# RF.net
KiCad netlist of a schematic drawn in Altium Designer
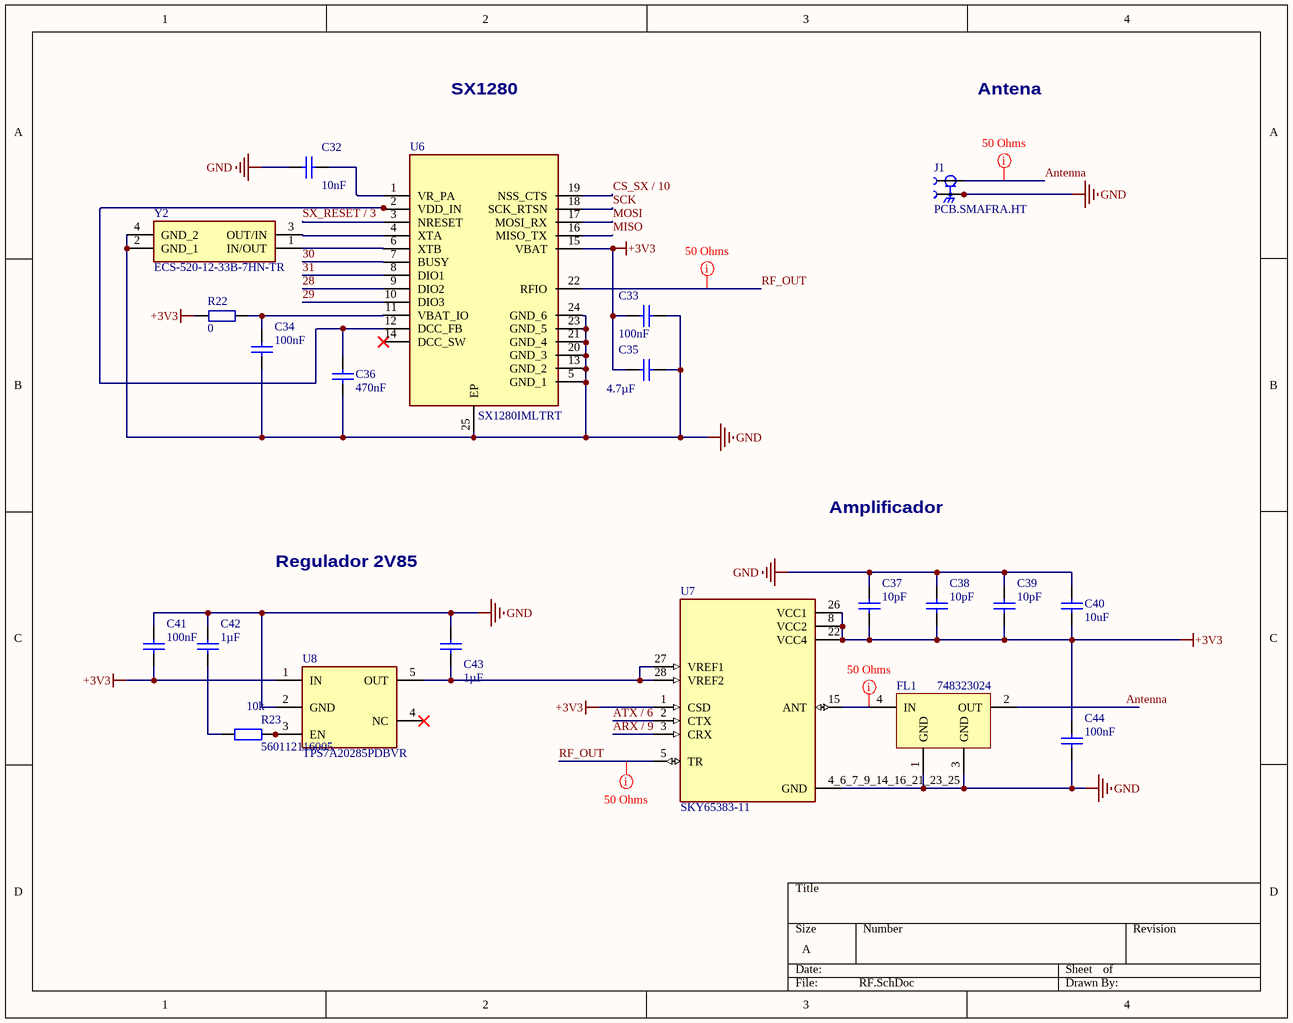
[diagram p0:  RF.SchDoc]

(export (version "E")
  (design (tool "Eeschema 10.0.6"))
  (components
    (comp (ref "C32")
      (value "10nF")
      (footprint "WCAP-CSGP_0603_L1.6W0.8H0.8_Reflow")
      (description "WCAP-CSGP Multilayer Ceramic Chip Capacitor, General Purpose, size 0603, X7R, 10nF, 25VDC")
      (fields
        (field (name "MANUFACTURER") "Wurth Elektronik")
        (field (name "MANUFACTURER PART NUMBER") "885012206065")
      )
      (libsource (lib "LEEM UPM") (part "885012209047R"))
    )
    (comp (ref "C33")
      (value "100nF")
      (footprint "WCAP-CSGP_0603_L1.6W0.8H0.8_Reflow")
      (description "WCAP-CSGP Multilayer Ceramic Chip Capacitor, General Purpose, size 0603, X7R, 100nF, 25VDC")
      (fields
        (field (name "MANUFACTURER") "Wurth Elektronik")
        (field (name "MANUFACTURER PART NUMBER") "885012206071")
      )
      (libsource (lib "LEEM UPM") (part "885012209047R"))
    )
    (comp (ref "C34")
      (value "100nF")
      (footprint "WCAP-CSGP_0603_L1.6W0.8H0.8_Reflow")
      (description "WCAP-CSGP Multilayer Ceramic Chip Capacitor, General Purpose, size 0603, X7R, 100nF, 25VDC")
      (fields
        (field (name "MANUFACTURER") "Wurth Elektronik")
        (field (name "MANUFACTURER PART NUMBER") "885012206071")
      )
      (libsource (lib "LEEM UPM") (part "885012209047R"))
    )
    (comp (ref "C35")
      (value "4.7µF")
      (footprint "WCAP-CSGP_0603_L1.6W0.8H0.8_Reflow")
      (description "WCAP-CSGP Multilayer Ceramic Chip Capacitor, General Purpose, size 0603, X5R, 4.7uF, 10VDC")
      (fields
        (field (name "MANUFACTURER PART NUMBER") "885012106012")
        (field (name "MANUFACTURER") "Wurth Elektronik")
      )
      (libsource (lib "LEEM UPM") (part "885012209047R"))
    )
    (comp (ref "C36")
      (value "470nF")
      (footprint "MY_0603")
      (description "None polar capacitor")
      (fields (field (name "ASID PART NUMBER") "C-AS") (field (name "Comment") "Cap ceramic"))
      (libsource (lib "LEEM UPM") (part "Cap ceramic"))
    )
    (comp (ref "C37")
      (value "10pF")
      (footprint "WCAP-CSGP_0603_L1.6W0.8H0.8_Reflow")
      (description "WCAP-CSGP Multilayer Ceramic Chip Capacitor, General Purpose, size 0603, NP0, 10pF, 50VDC")
      (fields
        (field (name "MANUFACTURER") "Wurth Elektronik")
        (field (name "MANUFACTURER PART NUMBER") "885012006051")
      )
      (libsource (lib "LEEM UPM") (part "885012209047R"))
    )
    (comp (ref "C38")
      (value "10pF")
      (footprint "WCAP-CSGP_0603_L1.6W0.8H0.8_Reflow")
      (description "WCAP-CSGP Multilayer Ceramic Chip Capacitor, General Purpose, size 0603, NP0, 10pF, 50VDC")
      (fields
        (field (name "MANUFACTURER") "Wurth Elektronik")
        (field (name "MANUFACTURER PART NUMBER") "885012006051")
      )
      (libsource (lib "LEEM UPM") (part "885012209047R"))
    )
    (comp (ref "C39")
      (value "10pF")
      (footprint "WCAP-CSGP_0603_L1.6W0.8H0.8_Reflow")
      (description "WCAP-CSGP Multilayer Ceramic Chip Capacitor, General Purpose, size 0603, NP0, 10pF, 50VDC")
      (fields
        (field (name "MANUFACTURER") "Wurth Elektronik")
        (field (name "MANUFACTURER PART NUMBER") "885012006051")
      )
      (libsource (lib "LEEM UPM") (part "885012209047R"))
    )
    (comp (ref "C40")
      (value "10uF")
      (footprint "MY_0603")
      (description "None polar capacitor")
      (fields (field (name "ASID PART NUMBER") "C-AS") (field (name "Comment") "Cap ceramic"))
      (libsource (lib "LEEM UPM") (part "Cap ceramic"))
    )
    (comp (ref "C41")
      (value "100nF")
      (footprint "WCAP-CSGP_0603_L1.6W0.8H0.8_Reflow")
      (description "WCAP-CSGP Multilayer Ceramic Chip Capacitor, General Purpose, size 0603, X7R, 100nF, 25VDC")
      (fields
        (field (name "MANUFACTURER") "Wurth Elektronik")
        (field (name "MANUFACTURER PART NUMBER") "885012206071")
      )
      (libsource (lib "LEEM UPM") (part "885012209047R"))
    )
    (comp (ref "C42")
      (value "1µF")
      (footprint "WCAP-CSGP_0603_L1.6W0.8H0.8_Reflow")
      (description "WCAP-CSGP Multilayer Ceramic Chip Capacitor, General Purpose, size 0603, X7R, 1uF, 16VDC")
      (fields
        (field (name "MANUFACTURER") "Wurth Elektronik")
        (field (name "MANUFACTURER PART NUMBER") "885012206052")
      )
      (libsource (lib "LEEM UPM") (part "885012209047R"))
    )
    (comp (ref "C43")
      (value "1µF")
      (footprint "WCAP-CSGP_0603_L1.6W0.8H0.8_Reflow")
      (description "WCAP-CSGP Multilayer Ceramic Chip Capacitor, General Purpose, size 0603, X7R, 1uF, 16VDC")
      (fields
        (field (name "MANUFACTURER") "Wurth Elektronik")
        (field (name "MANUFACTURER PART NUMBER") "885012206052")
      )
      (libsource (lib "LEEM UPM") (part "885012209047R"))
    )
    (comp (ref "C44")
      (value "100nF")
      (footprint "WCAP-CSGP_0603_L1.6W0.8H0.8_Reflow")
      (description "WCAP-CSGP Multilayer Ceramic Chip Capacitor, General Purpose, size 0603, X7R, 100nF, 25VDC")
      (fields
        (field (name "MANUFACTURER") "Wurth Elektronik")
        (field (name "MANUFACTURER PART NUMBER") "885012206071")
      )
      (libsource (lib "LEEM UPM") (part "885012209047R"))
    )
    (comp (ref "FL1")
      (value "748323024")
      (footprint "WE-BPF_0805")
      (description "Band Pass Filter")
      (libsource (lib "LEEM UPM") (part "WE-BPF"))
    )
    (comp (ref "J1")
      (value "PCB.SMAFRA.HT")
      (footprint "FP-PCB_SMAFRA_HT-MFG")
      (description "CONNSMAJACKR/A50OHMPCB")
      (libsource (lib "LEEM UPM") (part "9c40ac4d87bbbe9fcb330bd20f98ca3"))
    )
    (comp (ref "R22")
      (value "0")
      (footprint "R0603-0.45")
      (description "Resistor, generic")
      (libsource (lib "LEEM UPM") (part "RK73H2ALTD1004F"))
    )
    (comp (ref "R23")
      (value "560112116005")
      (footprint "WRIS-RSKS_0603_Reflow")
      (description "WRIS-RSKS Thick Film Resistor, size 0603, 10000Ohm, 100mW")
      (fields (field (name "ALTIUM_VALUE") "10k") (field (name "MANUFACTURER") "Wurth Elektronik"))
      (libsource (lib "LEEM UPM") (part "560112140010"))
    )
    (comp (ref "U6")
      (value "SX1280IMLTRT")
      (footprint "SX1280IMLTRT-Footprint-1")
      (description "Telecom Circuit")
      (libsource (lib "LEEM UPM") (part "SX1280IMLTRT"))
    )
    (comp (ref "U7")
      (value "SKY65383-11")
      (footprint "SKY65383-11-Footprint-1")
      (description "RF and Baseband Circuit")
      (libsource (lib "LEEM UPM") (part "SKY65383-11-Symbol-1"))
    )
    (comp (ref "U8")
      (value "TPS7A20285PDBVR")
      (footprint "TPS7A20285PDBVR-Footprint-1")
      (libsource (lib "LEEM UPM") (part "TPS7A20285PDBVR-Symbol-1"))
    )
    (comp (ref "Y2")
      (value "ECS-520-12-33B-7HN-TR")
      (footprint "ECS-520-12-33B-7HN-TR-Footprint-1")
      (description "Crystals 52.000 MHz 12 pF ECS-33B +/-7/15 ppm -40 - +85C +/-1 ppm Aging 3225 4-SMD RoHS")
      (libsource (lib "LEEM UPM") (part "ECS-520-12-33B-7HN-TR"))
    )
  )
  (nets
    (net (code "1") (name "+3V3") (class "Default")
      (node (ref "C33") (pin "1") (pinfunction "1_1") (pintype "passive"))
      (node (ref "C35") (pin "1") (pinfunction "1_1") (pintype "passive"))
      (node (ref "C37") (pin "2") (pinfunction "2_2") (pintype "passive"))
      (node (ref "C38") (pin "2") (pinfunction "2_2") (pintype "passive"))
      (node (ref "C39") (pin "2") (pinfunction "2_2") (pintype "passive"))
      (node (ref "C40") (pin "2") (pinfunction "2_2") (pintype "passive"))
      (node (ref "C41") (pin "2") (pinfunction "2_2") (pintype "passive"))
      (node (ref "C44") (pin "1") (pinfunction "1_1") (pintype "passive"))
      (node (ref "R22") (pin "1") (pinfunction "1_1") (pintype "passive"))
      (node (ref "U6") (pin "15") (pinfunction "VBAT_15") (pintype "passive"))
      (node (ref "U7") (pin "1") (pinfunction "CSD_1") (pintype "input"))
      (node (ref "U7") (pin "22") (pinfunction "VCC4_22") (pintype "power_in"))
      (node (ref "U7") (pin "26") (pinfunction "VCC1_26") (pintype "power_in"))
      (node (ref "U7") (pin "8") (pinfunction "VCC2_8") (pintype "power_in"))
      (node (ref "U8") (pin "1") (pinfunction "IN_1") (pintype "power_in"))
    )
    (net (code "2") (name "/28") (class "Default")
      (node (ref "U6") (pin "9") (pinfunction "DIO2_9") (pintype "passive"))
    )
    (net (code "3") (name "/29") (class "Default")
      (node (ref "U6") (pin "10") (pinfunction "DIO3_10") (pintype "passive"))
    )
    (net (code "4") (name "/30") (class "Default")
      (node (ref "U6") (pin "7") (pinfunction "BUSY_7") (pintype "passive"))
    )
    (net (code "5") (name "/31") (class "Default")
      (node (ref "U6") (pin "8") (pinfunction "DIO1_8") (pintype "passive"))
    )
    (net (code "6") (name "/ARX {slash} 9") (class "Default")
      (node (ref "U7") (pin "3") (pinfunction "CRX_3") (pintype "input"))
    )
    (net (code "7") (name "/ATX {slash} 6") (class "Default")
      (node (ref "U7") (pin "2") (pinfunction "CTX_2") (pintype "input"))
    )
    (net (code "8") (name "/Antenna") (class "Default")
      (node (ref "FL1") (pin "2") (pinfunction "OUT_2") (pintype "passive"))
      (node (ref "J1") (pin "1") (pinfunction "1_1") (pintype "passive"))
    )
    (net (code "9") (name "/CS_SX {slash} 10") (class "Default")
      (node (ref "U6") (pin "19") (pinfunction "NSS_CTS_19") (pintype "passive"))
    )
    (net (code "10") (name "/MISO") (class "Default")
      (node (ref "U6") (pin "16") (pinfunction "MISO_TX_16") (pintype "passive"))
    )
    (net (code "11") (name "/MOSI") (class "Default")
      (node (ref "U6") (pin "17") (pinfunction "MOSI_RX_17") (pintype "passive"))
    )
    (net (code "12") (name "/RF_OUT") (class "Default")
      (node (ref "U6") (pin "22") (pinfunction "RFIO_22") (pintype "passive"))
      (node (ref "U7") (pin "5") (pinfunction "TR_5") (pintype "bidirectional"))
    )
    (net (code "13") (name "/SCK") (class "Default")
      (node (ref "U6") (pin "18") (pinfunction "SCK_RTSN_18") (pintype "passive"))
    )
    (net (code "14") (name "/SX_RESET {slash} 3") (class "Default")
      (node (ref "U6") (pin "3") (pinfunction "NRESET_3") (pintype "passive"))
    )
    (net (code "15") (name "GND") (class "Default")
      (node (ref "C32") (pin "2") (pinfunction "2_2") (pintype "passive"))
      (node (ref "C33") (pin "2") (pinfunction "2_2") (pintype "passive"))
      (node (ref "C34") (pin "2") (pinfunction "2_2") (pintype "passive"))
      (node (ref "C35") (pin "2") (pinfunction "2_2") (pintype "passive"))
      (node (ref "C36") (pin "2") (pinfunction "2_2") (pintype "passive"))
      (node (ref "C37") (pin "1") (pinfunction "1_1") (pintype "passive"))
      (node (ref "C38") (pin "1") (pinfunction "1_1") (pintype "passive"))
      (node (ref "C39") (pin "1") (pinfunction "1_1") (pintype "passive"))
      (node (ref "C40") (pin "1") (pinfunction "1_1") (pintype "passive"))
      (node (ref "C41") (pin "1") (pinfunction "1_1") (pintype "passive"))
      (node (ref "C42") (pin "1") (pinfunction "1_1") (pintype "passive"))
      (node (ref "C43") (pin "2") (pinfunction "2_2") (pintype "passive"))
      (node (ref "C44") (pin "2") (pinfunction "2_2") (pintype "passive"))
      (node (ref "FL1") (pin "1") (pinfunction "GND_1") (pintype "passive"))
      (node (ref "FL1") (pin "3") (pinfunction "GND_3") (pintype "passive"))
      (node (ref "J1") (pin "S1") (pinfunction "2_S1") (pintype "passive"))
      (node (ref "J1") (pin "S2") (pinfunction "2_S2") (pintype "passive"))
      (node (ref "J1") (pin "S3") (pinfunction "2_S3") (pintype "passive"))
      (node (ref "J1") (pin "S4") (pinfunction "2_S4") (pintype "passive"))
      (node (ref "U6") (pin "13") (pinfunction "GND_2_13") (pintype "passive"))
      (node (ref "U6") (pin "20") (pinfunction "GND_3_20") (pintype "passive"))
      (node (ref "U6") (pin "21") (pinfunction "GND_4_21") (pintype "passive"))
      (node (ref "U6") (pin "23") (pinfunction "GND_5_23") (pintype "passive"))
      (node (ref "U6") (pin "24") (pinfunction "GND_6_24") (pintype "passive"))
      (node (ref "U6") (pin "25") (pinfunction "EP_25") (pintype "passive"))
      (node (ref "U6") (pin "5") (pinfunction "GND_1_5") (pintype "passive"))
      (node (ref "U7") (pin "4_6_7_9_14_16_21_23_25") (pinfunction "GND_4_6_7_9_14_16_21_23_25") (pintype "power_in"))
      (node (ref "U8") (pin "2") (pinfunction "GND_2") (pintype "passive"))
      (node (ref "Y2") (pin "2") (pinfunction "GND_1_2") (pintype "passive"))
      (node (ref "Y2") (pin "4") (pinfunction "GND_2_4") (pintype "passive"))
    )
    (net (code "16") (name "Net-(C42-Pad2)") (class "Default")
      (node (ref "C42") (pin "2") (pinfunction "2_2") (pintype "passive"))
      (node (ref "R23") (pin "2") (pinfunction "2_2") (pintype "passive"))
    )
    (net (code "17") (name "Net-(FL1-IN)") (class "Default")
      (node (ref "FL1") (pin "4") (pinfunction "IN_4") (pintype "passive"))
      (node (ref "U7") (pin "15") (pinfunction "ANT_15") (pintype "bidirectional"))
    )
    (net (code "18") (name "Net-(U6-DCC_FB)") (class "Default")
      (node (ref "C36") (pin "1") (pinfunction "1_1") (pintype "passive"))
      (node (ref "U6") (pin "12") (pinfunction "DCC_FB_12") (pintype "passive"))
      (node (ref "U6") (pin "2") (pinfunction "VDD_IN_2") (pintype "passive"))
    )
    (net (code "19") (name "Net-(U6-VBAT_IO)") (class "Default")
      (node (ref "C34") (pin "1") (pinfunction "1_1") (pintype "passive"))
      (node (ref "R22") (pin "2") (pinfunction "2_2") (pintype "passive"))
      (node (ref "U6") (pin "11") (pinfunction "VBAT_IO_11") (pintype "passive"))
    )
    (net (code "20") (name "Net-(U6-VR_PA)") (class "Default")
      (node (ref "C32") (pin "1") (pinfunction "1_1") (pintype "passive"))
      (node (ref "U6") (pin "1") (pinfunction "VR_PA_1") (pintype "passive"))
    )
    (net (code "21") (name "Net-(U6-XTA)") (class "Default")
      (node (ref "U6") (pin "4") (pinfunction "XTA_4") (pintype "passive"))
      (node (ref "Y2") (pin "3") (pinfunction "OUT/IN_3") (pintype "passive"))
    )
    (net (code "22") (name "Net-(U6-XTB)") (class "Default")
      (node (ref "U6") (pin "6") (pinfunction "XTB_6") (pintype "passive"))
      (node (ref "Y2") (pin "1") (pinfunction "IN/OUT_1") (pintype "passive"))
    )
    (net (code "23") (name "Net-(U7-VREF1)") (class "Default")
      (node (ref "C43") (pin "1") (pinfunction "1_1") (pintype "passive"))
      (node (ref "U7") (pin "27") (pinfunction "VREF1_27") (pintype "input"))
      (node (ref "U7") (pin "28") (pinfunction "VREF2_28") (pintype "input"))
      (node (ref "U8") (pin "5") (pinfunction "OUT_5") (pintype "passive"))
    )
    (net (code "24") (name "Net-(U8-EN)") (class "Default")
      (node (ref "R23") (pin "1") (pinfunction "1_1") (pintype "passive"))
      (node (ref "U8") (pin "3") (pinfunction "EN_3") (pintype "passive"))
    )
    (net (code "25") (name "unconnected-(U6-DCC_SW-Pad14)") (class "Default")
      (node (ref "U6") (pin "14") (pinfunction "DCC_SW_14") (pintype "passive+no_connect"))
    )
    (net (code "26") (name "unconnected-(U8-NC-Pad4)") (class "Default")
      (node (ref "U8") (pin "4") (pinfunction "NC_4") (pintype "passive+no_connect"))
    )
  )
)
